# RGMII_SDIO_I2S.net
KiCad netlist of a schematic drawn in Altium Designer
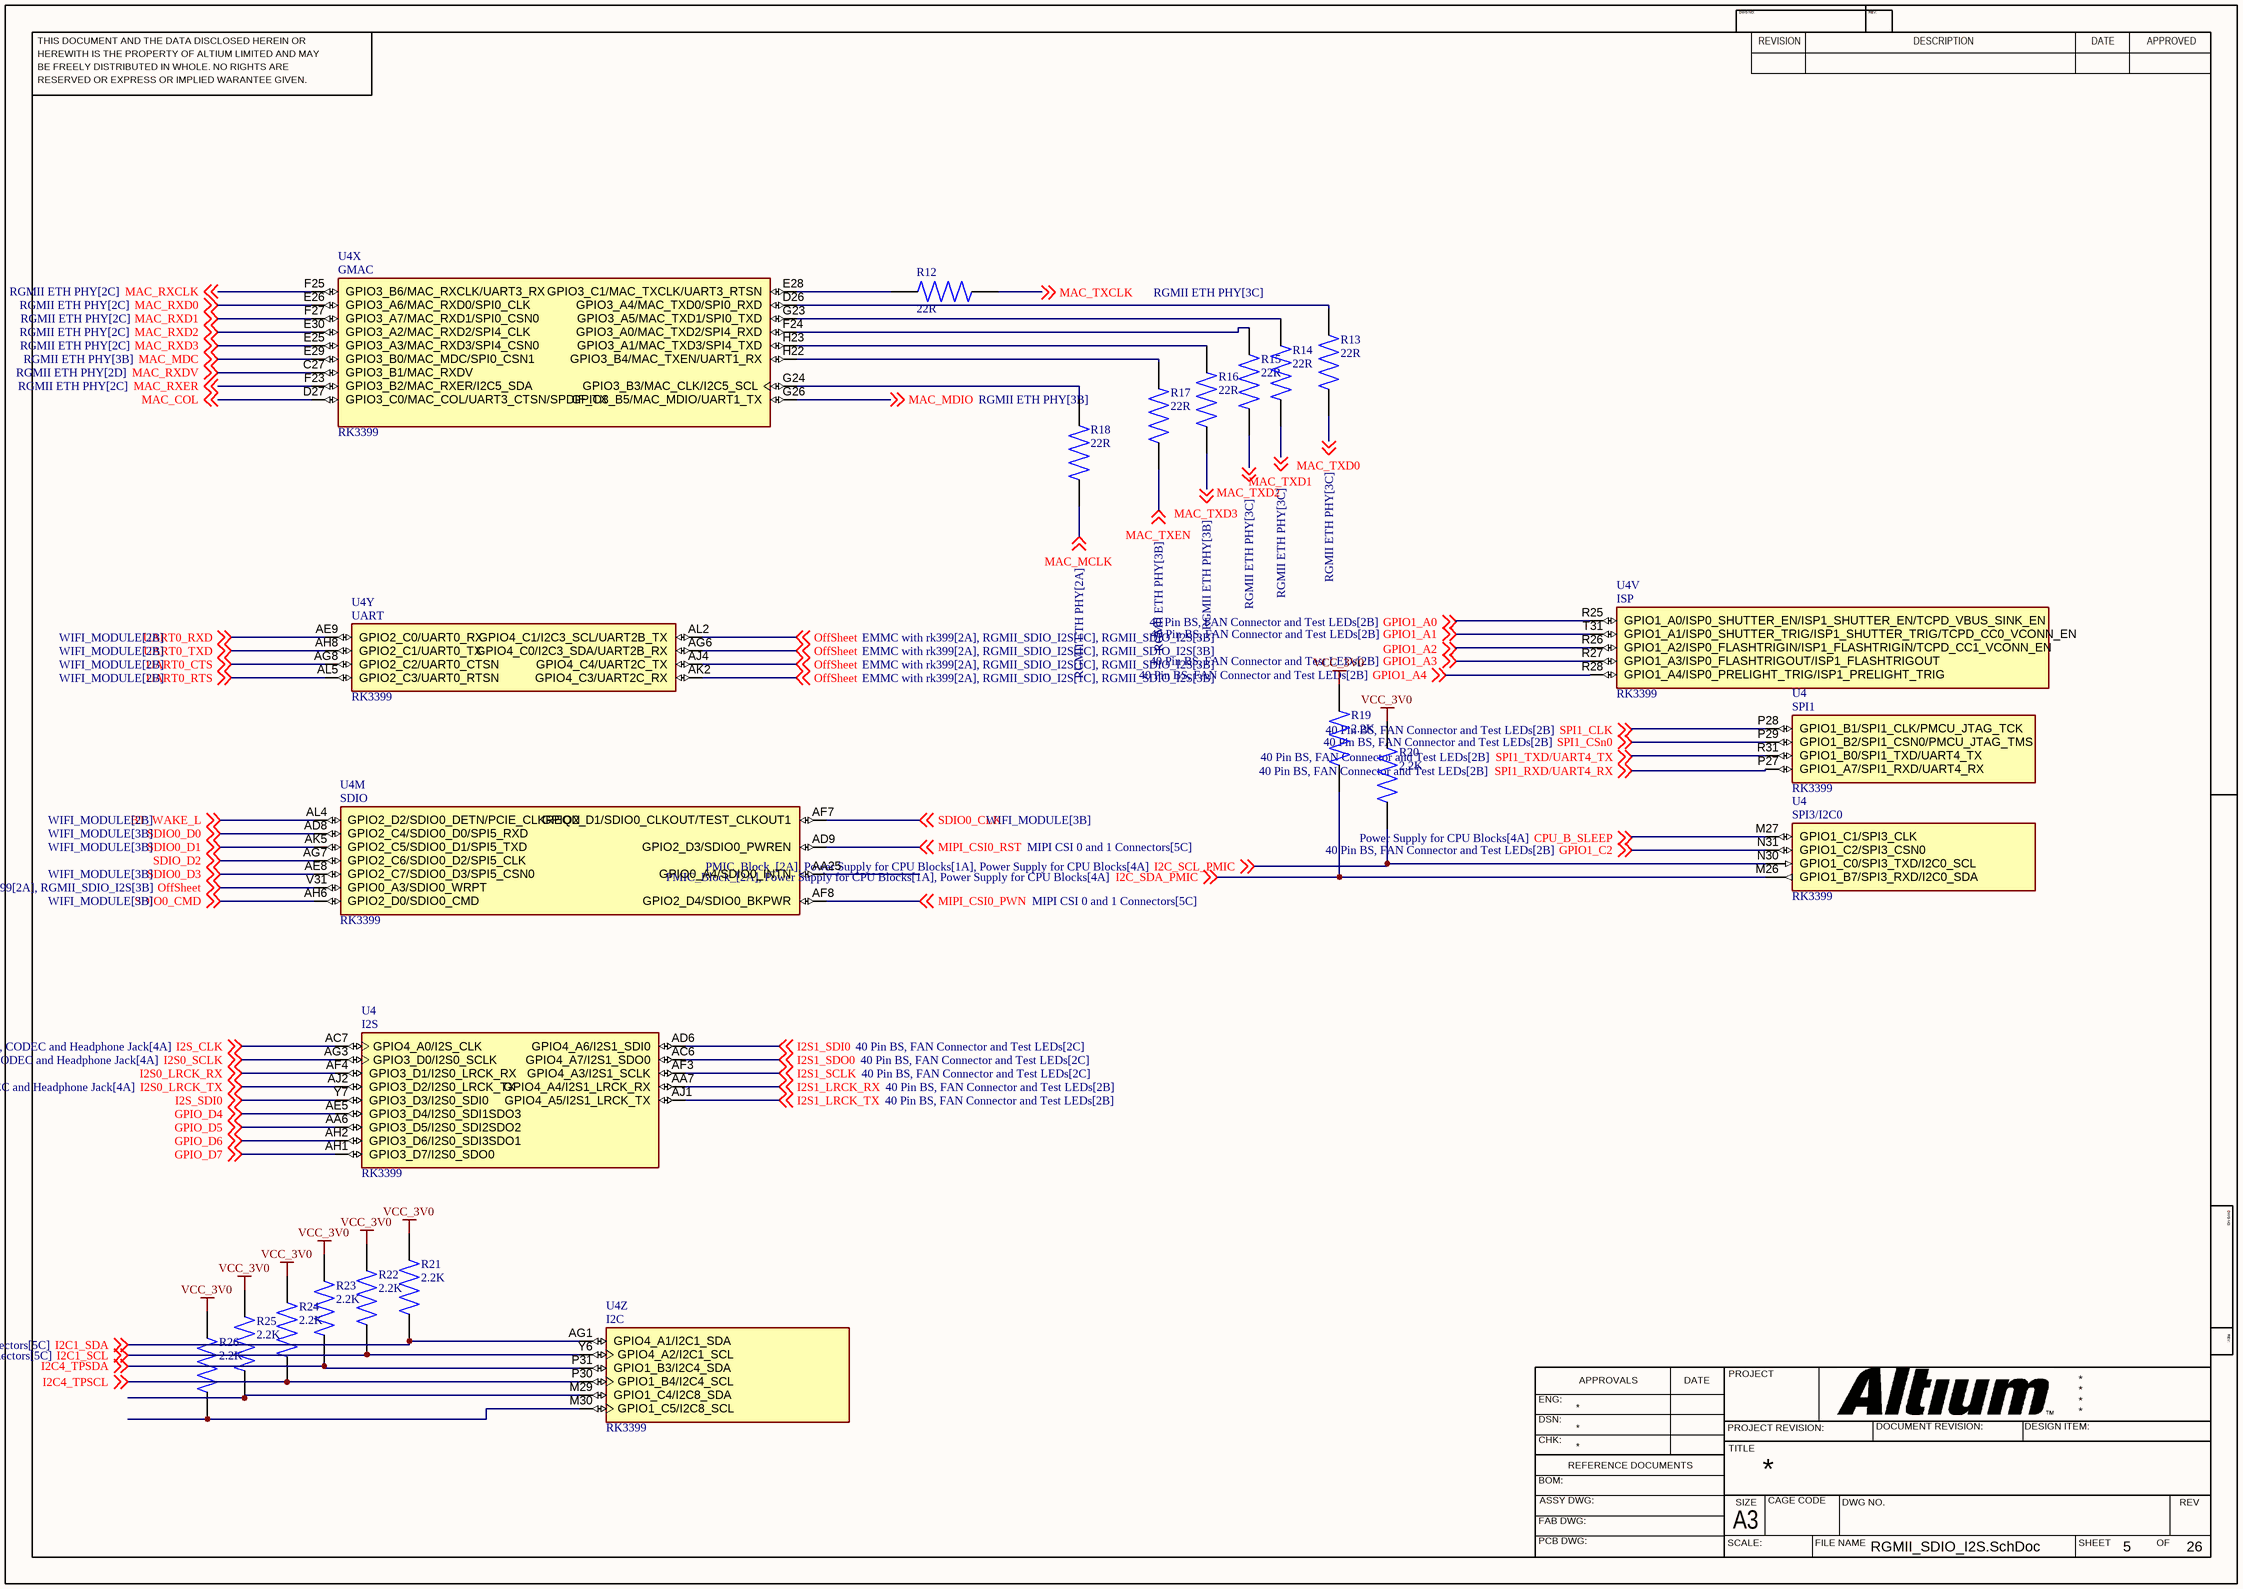
[diagram p0: RGMII_SDIO_I2S.SchDoc]

(export (version "E")
  (design (tool "Eeschema 10.0.6"))
  (components
    (comp (ref "R12")
      (value "22R")
      (footprint "RES_ERA6AHD330V")
      (fields (field (name "MP") "ERA6AHD330V"))
      (libsource (lib "ERA6AHD330V") (part "ERA6AHD330V"))
    )
    (comp (ref "R13")
      (value "22R")
      (footprint "RES_ERA6AHD330V")
      (fields (field (name "MP") "ERA6AHD330V"))
      (libsource (lib "ERA6AHD330V") (part "ERA6AHD330V"))
    )
    (comp (ref "R14")
      (value "22R")
      (footprint "RES_ERA6AHD330V")
      (fields (field (name "MP") "ERA6AHD330V"))
      (libsource (lib "ERA6AHD330V") (part "ERA6AHD330V"))
    )
    (comp (ref "R15")
      (value "22R")
      (footprint "RES_ERA6AHD330V")
      (fields (field (name "MP") "ERA6AHD330V"))
      (libsource (lib "ERA6AHD330V") (part "ERA6AHD330V"))
    )
    (comp (ref "R16")
      (value "22R")
      (footprint "RES_ERA6AHD330V")
      (fields (field (name "MP") "ERA6AHD330V"))
      (libsource (lib "ERA6AHD330V") (part "ERA6AHD330V"))
    )
    (comp (ref "R17")
      (value "22R")
      (footprint "RES_ERA6AHD330V")
      (fields (field (name "MP") "ERA6AHD330V"))
      (libsource (lib "ERA6AHD330V") (part "ERA6AHD330V"))
    )
    (comp (ref "R18")
      (value "22R")
      (footprint "RES_ERA6AHD330V")
      (fields (field (name "MP") "ERA6AHD330V"))
      (libsource (lib "ERA6AHD330V") (part "ERA6AHD330V"))
    )
    (comp (ref "R19")
      (value "2.2K")
      (footprint "RES_ERA8APB222V")
      (fields (field (name "MP") "ERA8APB222V"))
      (libsource (lib "ERA8APB222V") (part "ERA8APB222V"))
    )
    (comp (ref "R20")
      (value "2.2K")
      (footprint "RES_ERA8APB222V")
      (fields (field (name "MP") "ERA8APB222V"))
      (libsource (lib "ERA8APB222V") (part "ERA8APB222V"))
    )
    (comp (ref "R21")
      (value "2.2K")
      (footprint "RES_ERA8APB222V")
      (fields (field (name "MP") "ERA8APB222V"))
      (libsource (lib "ERA8APB222V") (part "ERA8APB222V"))
    )
    (comp (ref "R22")
      (value "2.2K")
      (footprint "RES_ERA8APB222V")
      (fields (field (name "MP") "ERA8APB222V"))
      (libsource (lib "ERA8APB222V") (part "ERA8APB222V"))
    )
    (comp (ref "R23")
      (value "2.2K")
      (footprint "RES_ERA8APB222V")
      (fields (field (name "MP") "ERA8APB222V"))
      (libsource (lib "ERA8APB222V") (part "ERA8APB222V"))
    )
    (comp (ref "R24")
      (value "2.2K")
      (footprint "RES_ERA8APB222V")
      (fields (field (name "MP") "ERA8APB222V"))
      (libsource (lib "ERA8APB222V") (part "ERA8APB222V"))
    )
    (comp (ref "R25")
      (value "2.2K")
      (footprint "RES_ERA8APB222V")
      (fields (field (name "MP") "ERA8APB222V"))
      (libsource (lib "ERA8APB222V") (part "ERA8APB222V"))
    )
    (comp (ref "R26")
      (value "2.2K")
      (footprint "RES_ERA8APB222V")
      (fields (field (name "MP") "ERA8APB222V"))
      (libsource (lib "ERA8APB222V") (part "ERA8APB222V"))
    )
    (comp (ref "U4")
      (value "RK3399")
      (footprint "BGA828C65P31X31_2100X2100X161N")
      (description "RK3399 ROCK Pi 4 Model A 2GB - ARMÂ® CortexÂ®-A53, CortexÂ®-A72 MPU Embedded Evaluation Board")
      (fields (field (name "MF") "Rockchip"))
      (libsource (lib "RK3399") (part "RK3399"))
    )
  )
  (nets
    (net (code "1") (name "BT_WAKE_L") (class "Default")
      (node (ref "U4") (pin "AL4") (pinfunction "GPIO2_D2/SDIO0_DETN/PCIE_CLKREQN_AL4") (pintype "bidirectional"))
    )
    (net (code "2") (name "CPU_B_SLEEP") (class "Default")
      (node (ref "U4") (pin "M27") (pinfunction "GPIO1_C1/SPI3_CLK_M27") (pintype "bidirectional"))
    )
    (net (code "3") (name "GPIO1_A0") (class "Default")
      (node (ref "U4") (pin "R25") (pinfunction "GPIO1_A0/ISP0_SHUTTER_EN/ISP1_SHUTTER_EN/TCPD_VBUS_SINK_EN_R25") (pintype "bidirectional"))
    )
    (net (code "4") (name "GPIO1_A1") (class "Default")
      (node (ref "U4") (pin "T31") (pinfunction "GPIO1_A1/ISP0_SHUTTER_TRIG/ISP1_SHUTTER_TRIG/TCPD_CC0_VCONN_EN_T31") (pintype "bidirectional"))
    )
    (net (code "5") (name "GPIO1_A2") (class "Default")
      (node (ref "U4") (pin "R26") (pinfunction "GPIO1_A2/ISP0_FLASHTRIGIN/ISP1_FLASHTRIGIN/TCPD_CC1_VCONN_EN_R26") (pintype "bidirectional"))
    )
    (net (code "6") (name "GPIO1_A3") (class "Default")
      (node (ref "U4") (pin "R27") (pinfunction "GPIO1_A3/ISP0_FLASHTRIGOUT/ISP1_FLASHTRIGOUT_R27") (pintype "bidirectional"))
    )
    (net (code "7") (name "GPIO1_A4") (class "Default")
      (node (ref "U4") (pin "R28") (pinfunction "GPIO1_A4/ISP0_PRELIGHT_TRIG/ISP1_PRELIGHT_TRIG_R28") (pintype "bidirectional"))
    )
    (net (code "8") (name "GPIO1_C2") (class "Default")
      (node (ref "U4") (pin "N31") (pinfunction "GPIO1_C2/SPI3_CSN0_N31") (pintype "bidirectional"))
    )
    (net (code "9") (name "GPIO_D4") (class "Default")
      (node (ref "U4") (pin "AE5") (pinfunction "GPIO3_D4/I2S0_SDI1SDO3_AE5") (pintype "bidirectional"))
    )
    (net (code "10") (name "GPIO_D5") (class "Default")
      (node (ref "U4") (pin "AA6") (pinfunction "GPIO3_D5/I2S0_SDI2SDO2_AA6") (pintype "bidirectional"))
    )
    (net (code "11") (name "GPIO_D6") (class "Default")
      (node (ref "U4") (pin "AH2") (pinfunction "GPIO3_D6/I2S0_SDI3SDO1_AH2") (pintype "bidirectional"))
    )
    (net (code "12") (name "GPIO_D7") (class "Default")
      (node (ref "U4") (pin "AH1") (pinfunction "GPIO3_D7/I2S0_SDO0_AH1") (pintype "bidirectional"))
    )
    (net (code "13") (name "I2C1_SCL") (class "Default")
      (node (ref "R22") (pin "1") (pinfunction "1_1") (pintype "passive"))
      (node (ref "U4") (pin "Y6") (pinfunction "GPIO4_A2/I2C1_SCL_Y6") (pintype "bidirectional"))
    )
    (net (code "14") (name "I2C1_SDA") (class "Default")
      (node (ref "R21") (pin "1") (pinfunction "1_1") (pintype "passive"))
      (node (ref "U4") (pin "AG1") (pinfunction "GPIO4_A1/I2C1_SDA_AG1") (pintype "bidirectional"))
    )
    (net (code "15") (name "I2C4_TPSCL") (class "Default")
      (node (ref "R24") (pin "1") (pinfunction "1_1") (pintype "passive"))
      (node (ref "U4") (pin "P30") (pinfunction "GPIO1_B4/I2C4_SCL_P30") (pintype "bidirectional"))
    )
    (net (code "16") (name "I2C4_TPSDA") (class "Default")
      (node (ref "R23") (pin "1") (pinfunction "1_1") (pintype "passive"))
      (node (ref "U4") (pin "P31") (pinfunction "GPIO1_B3/I2C4_SDA_P31") (pintype "bidirectional"))
    )
    (net (code "17") (name "I2C_SCL_PMIC") (class "Default")
      (node (ref "R20") (pin "1") (pinfunction "1_1") (pintype "passive"))
      (node (ref "U4") (pin "N30") (pinfunction "GPIO1_C0/SPI3_TXD/I2C0_SCL_N30") (pintype "input"))
    )
    (net (code "18") (name "I2C_SDA_PMIC") (class "Default")
      (node (ref "R19") (pin "1") (pinfunction "1_1") (pintype "passive"))
      (node (ref "U4") (pin "M26") (pinfunction "GPIO1_B7/SPI3_RXD/I2C0_SDA_M26") (pintype "output"))
    )
    (net (code "19") (name "I2S0_LRCK_RX") (class "Default")
      (node (ref "U4") (pin "AF4") (pinfunction "GPIO3_D1/I2S0_LRCK_RX_AF4") (pintype "bidirectional"))
    )
    (net (code "20") (name "I2S0_LRCK_TX") (class "Default")
      (node (ref "U4") (pin "AJ2") (pinfunction "GPIO3_D2/I2S0_LRCK_TX_AJ2") (pintype "bidirectional"))
    )
    (net (code "21") (name "I2S0_SCLK") (class "Default")
      (node (ref "U4") (pin "AG3") (pinfunction "GPIO3_D0/I2S0_SCLK_AG3") (pintype "bidirectional"))
    )
    (net (code "22") (name "I2S1_LRCK_RX") (class "Default")
      (node (ref "U4") (pin "AA7") (pinfunction "GPIO4_A4/I2S1_LRCK_RX_AA7") (pintype "bidirectional"))
    )
    (net (code "23") (name "I2S1_LRCK_TX") (class "Default")
      (node (ref "U4") (pin "AJ1") (pinfunction "GPIO4_A5/I2S1_LRCK_TX_AJ1") (pintype "bidirectional"))
    )
    (net (code "24") (name "I2S1_SCLK") (class "Default")
      (node (ref "U4") (pin "AF3") (pinfunction "GPIO4_A3/I2S1_SCLK_AF3") (pintype "bidirectional"))
    )
    (net (code "25") (name "I2S1_SDI0") (class "Default")
      (node (ref "U4") (pin "AD6") (pinfunction "GPIO4_A6/I2S1_SDI0_AD6") (pintype "bidirectional"))
    )
    (net (code "26") (name "I2S1_SDO0") (class "Default")
      (node (ref "U4") (pin "AC6") (pinfunction "GPIO4_A7/I2S1_SDO0_AC6") (pintype "bidirectional"))
    )
    (net (code "27") (name "I2S_CLK") (class "Default")
      (node (ref "U4") (pin "AC7") (pinfunction "GPIO4_A0/I2S_CLK_AC7") (pintype "bidirectional"))
    )
    (net (code "28") (name "I2S_SDI0") (class "Default")
      (node (ref "U4") (pin "Y7") (pinfunction "GPIO3_D3/I2S0_SDI0_Y7") (pintype "bidirectional"))
    )
    (net (code "29") (name "MAC_COL") (class "Default")
      (node (ref "U4") (pin "D27") (pinfunction "GPIO3_C0/MAC_COL/UART3_CTSN/SPDIF_TX_D27") (pintype "bidirectional"))
    )
    (net (code "30") (name "MAC_MCLK") (class "Default")
      (node (ref "R18") (pin "1") (pinfunction "1_1") (pintype "passive"))
    )
    (net (code "31") (name "MAC_MDC") (class "Default")
      (node (ref "U4") (pin "E29") (pinfunction "GPIO3_B0/MAC_MDC/SPI0_CSN1_E29") (pintype "bidirectional"))
    )
    (net (code "32") (name "MAC_MDIO") (class "Default")
      (node (ref "U4") (pin "G26") (pinfunction "GPIO3_B5/MAC_MDIO/UART1_TX_G26") (pintype "bidirectional"))
    )
    (net (code "33") (name "MAC_RXCLK") (class "Default")
      (node (ref "U4") (pin "F25") (pinfunction "GPIO3_B6/MAC_RXCLK/UART3_RX_F25") (pintype "bidirectional"))
    )
    (net (code "34") (name "MAC_RXD0") (class "Default")
      (node (ref "U4") (pin "E26") (pinfunction "GPIO3_A6/MAC_RXD0/SPI0_CLK_E26") (pintype "bidirectional"))
    )
    (net (code "35") (name "MAC_RXD1") (class "Default")
      (node (ref "U4") (pin "F27") (pinfunction "GPIO3_A7/MAC_RXD1/SPI0_CSN0_F27") (pintype "bidirectional"))
    )
    (net (code "36") (name "MAC_RXD2") (class "Default")
      (node (ref "U4") (pin "E30") (pinfunction "GPIO3_A2/MAC_RXD2/SPI4_CLK_E30") (pintype "bidirectional"))
    )
    (net (code "37") (name "MAC_RXD3") (class "Default")
      (node (ref "U4") (pin "E25") (pinfunction "GPIO3_A3/MAC_RXD3/SPI4_CSN0_E25") (pintype "bidirectional"))
    )
    (net (code "38") (name "MAC_RXDV") (class "Default")
      (node (ref "U4") (pin "C27") (pinfunction "GPIO3_B1/MAC_RXDV_C27") (pintype "bidirectional"))
    )
    (net (code "39") (name "MAC_RXER") (class "Default")
      (node (ref "U4") (pin "F23") (pinfunction "GPIO3_B2/MAC_RXER/I2C5_SDA_F23") (pintype "bidirectional"))
    )
    (net (code "40") (name "MAC_TXCLK") (class "Default")
      (node (ref "R12") (pin "1") (pinfunction "1_1") (pintype "passive"))
    )
    (net (code "41") (name "MAC_TXD0") (class "Default")
      (node (ref "R13") (pin "1") (pinfunction "1_1") (pintype "passive"))
    )
    (net (code "42") (name "MAC_TXD1") (class "Default")
      (node (ref "R14") (pin "1") (pinfunction "1_1") (pintype "passive"))
    )
    (net (code "43") (name "MAC_TXD2") (class "Default")
      (node (ref "R15") (pin "1") (pinfunction "1_1") (pintype "passive"))
    )
    (net (code "44") (name "MAC_TXD3") (class "Default")
      (node (ref "R16") (pin "1") (pinfunction "1_1") (pintype "passive"))
    )
    (net (code "45") (name "MAC_TXEN") (class "Default")
      (node (ref "R17") (pin "1") (pinfunction "1_1") (pintype "passive"))
    )
    (net (code "46") (name "MIPI_CSI0_PWN") (class "Default")
      (node (ref "U4") (pin "AF8") (pinfunction "GPIO2_D4/SDIO0_BKPWR_AF8") (pintype "bidirectional"))
    )
    (net (code "47") (name "MIPI_CSI0_RST") (class "Default")
      (node (ref "U4") (pin "AD9") (pinfunction "GPIO2_D3/SDIO0_PWREN_AD9") (pintype "bidirectional"))
    )
    (net (code "48") (name "Net-(U4X-GPIO3_A0{slash}MAC_TXD2{slash}SPI4_RXD)") (class "Default")
      (node (ref "R15") (pin "2") (pinfunction "2_2") (pintype "passive"))
      (node (ref "U4") (pin "F24") (pinfunction "GPIO3_A0/MAC_TXD2/SPI4_RXD_F24") (pintype "bidirectional"))
    )
    (net (code "49") (name "Net-(U4X-GPIO3_A1{slash}MAC_TXD3{slash}SPI4_TXD)") (class "Default")
      (node (ref "R16") (pin "2") (pinfunction "2_2") (pintype "passive"))
      (node (ref "U4") (pin "H23") (pinfunction "GPIO3_A1/MAC_TXD3/SPI4_TXD_H23") (pintype "bidirectional"))
    )
    (net (code "50") (name "Net-(U4X-GPIO3_A4{slash}MAC_TXD0{slash}SPI0_RXD)") (class "Default")
      (node (ref "R13") (pin "2") (pinfunction "2_2") (pintype "passive"))
      (node (ref "U4") (pin "D26") (pinfunction "GPIO3_A4/MAC_TXD0/SPI0_RXD_D26") (pintype "bidirectional"))
    )
    (net (code "51") (name "Net-(U4X-GPIO3_A5{slash}MAC_TXD1{slash}SPI0_TXD)") (class "Default")
      (node (ref "R14") (pin "2") (pinfunction "2_2") (pintype "passive"))
      (node (ref "U4") (pin "G23") (pinfunction "GPIO3_A5/MAC_TXD1/SPI0_TXD_G23") (pintype "bidirectional"))
    )
    (net (code "52") (name "Net-(U4X-GPIO3_B3{slash}MAC_CLK{slash}I2C5_SCL)") (class "Default")
      (node (ref "R18") (pin "2") (pinfunction "2_2") (pintype "passive"))
      (node (ref "U4") (pin "G24") (pinfunction "GPIO3_B3/MAC_CLK/I2C5_SCL_G24") (pintype "bidirectional"))
    )
    (net (code "53") (name "Net-(U4X-GPIO3_B4{slash}MAC_TXEN{slash}UART1_RX)") (class "Default")
      (node (ref "R17") (pin "2") (pinfunction "2_2") (pintype "passive"))
      (node (ref "U4") (pin "H22") (pinfunction "GPIO3_B4/MAC_TXEN/UART1_RX_H22") (pintype "bidirectional"))
    )
    (net (code "54") (name "Net-(U4X-GPIO3_C1{slash}MAC_TXCLK{slash}UART3_RTSN)") (class "Default")
      (node (ref "R12") (pin "2") (pinfunction "2_2") (pintype "passive"))
      (node (ref "U4") (pin "E28") (pinfunction "GPIO3_C1/MAC_TXCLK/UART3_RTSN_E28") (pintype "bidirectional"))
    )
    (net (code "55") (name "Net-(U4Z-GPIO1_C4{slash}I2C8_SDA)") (class "Default")
      (node (ref "R25") (pin "1") (pinfunction "1_1") (pintype "passive"))
      (node (ref "U4") (pin "M29") (pinfunction "GPIO1_C4/I2C8_SDA_M29") (pintype "bidirectional"))
    )
    (net (code "56") (name "Net-(U4Z-GPIO1_C5{slash}I2C8_SCL)") (class "Default")
      (node (ref "R26") (pin "1") (pinfunction "1_1") (pintype "passive"))
      (node (ref "U4") (pin "M30") (pinfunction "GPIO1_C5/I2C8_SCL_M30") (pintype "bidirectional"))
    )
    (net (code "57") (name "OffSheet") (class "Default")
      (node (ref "U4") (pin "AG6") (pinfunction "GPIO4_C0/I2C3_SDA/UART2B_RX_AG6") (pintype "bidirectional"))
      (node (ref "U4") (pin "AJ4") (pinfunction "GPIO4_C4/UART2C_TX_AJ4") (pintype "bidirectional"))
      (node (ref "U4") (pin "AK2") (pinfunction "GPIO4_C3/UART2C_RX_AK2") (pintype "bidirectional"))
      (node (ref "U4") (pin "AL2") (pinfunction "GPIO4_C1/I2C3_SCL/UART2B_TX_AL2") (pintype "bidirectional"))
      (node (ref "U4") (pin "V31") (pinfunction "GPIO0_A3/SDIO0_WRPT_V31") (pintype "bidirectional"))
    )
    (net (code "58") (name "SDIO0_CLK") (class "Default")
      (node (ref "U4") (pin "AF7") (pinfunction "GPIO2_D1/SDIO0_CLKOUT/TEST_CLKOUT1_AF7") (pintype "bidirectional"))
    )
    (net (code "59") (name "SDIO0_CMD") (class "Default")
      (node (ref "U4") (pin "AH6") (pinfunction "GPIO2_D0/SDIO0_CMD_AH6") (pintype "bidirectional"))
    )
    (net (code "60") (name "SDIO0_D0") (class "Default")
      (node (ref "U4") (pin "AD8") (pinfunction "GPIO2_C4/SDIO0_D0/SPI5_RXD_AD8") (pintype "bidirectional"))
    )
    (net (code "61") (name "SDIO0_D1") (class "Default")
      (node (ref "U4") (pin "AK5") (pinfunction "GPIO2_C5/SDIO0_D1/SPI5_TXD_AK5") (pintype "bidirectional"))
    )
    (net (code "62") (name "SDIO0_D3") (class "Default")
      (node (ref "U4") (pin "AE8") (pinfunction "GPIO2_C7/SDIO0_D3/SPI5_CSN0_AE8") (pintype "bidirectional"))
    )
    (net (code "63") (name "SDIO_D2") (class "Default")
      (node (ref "U4") (pin "AG7") (pinfunction "GPIO2_C6/SDIO0_D2/SPI5_CLK_AG7") (pintype "bidirectional"))
    )
    (net (code "64") (name "SPI1_CLK") (class "Default")
      (node (ref "U4") (pin "P28") (pinfunction "GPIO1_B1/SPI1_CLK/PMCU_JTAG_TCK_P28") (pintype "bidirectional"))
    )
    (net (code "65") (name "SPI1_CSn0") (class "Default")
      (node (ref "U4") (pin "P29") (pinfunction "GPIO1_B2/SPI1_CSN0/PMCU_JTAG_TMS_P29") (pintype "bidirectional"))
    )
    (net (code "66") (name "SPI1_RXD{slash}UART4_RX") (class "Default")
      (node (ref "U4") (pin "P27") (pinfunction "GPIO1_A7/SPI1_RXD/UART4_RX_P27") (pintype "bidirectional"))
    )
    (net (code "67") (name "SPI1_TXD{slash}UART4_TX") (class "Default")
      (node (ref "U4") (pin "R31") (pinfunction "GPIO1_B0/SPI1_TXD/UART4_TX_R31") (pintype "bidirectional"))
    )
    (net (code "68") (name "UART0_CTS") (class "Default")
      (node (ref "U4") (pin "AG8") (pinfunction "GPIO2_C2/UART0_CTSN_AG8") (pintype "bidirectional"))
    )
    (net (code "69") (name "UART0_RTS") (class "Default")
      (node (ref "U4") (pin "AL5") (pinfunction "GPIO2_C3/UART0_RTSN_AL5") (pintype "bidirectional"))
    )
    (net (code "70") (name "UART0_RXD") (class "Default")
      (node (ref "U4") (pin "AE9") (pinfunction "GPIO2_C0/UART0_RX_AE9") (pintype "bidirectional"))
    )
    (net (code "71") (name "UART0_TXD") (class "Default")
      (node (ref "U4") (pin "AH8") (pinfunction "GPIO2_C1/UART0_TX_AH8") (pintype "bidirectional"))
    )
    (net (code "72") (name "VCC_3V0") (class "Default")
      (node (ref "R19") (pin "2") (pinfunction "2_2") (pintype "passive"))
      (node (ref "R20") (pin "2") (pinfunction "2_2") (pintype "passive"))
      (node (ref "R21") (pin "2") (pinfunction "2_2") (pintype "passive"))
      (node (ref "R22") (pin "2") (pinfunction "2_2") (pintype "passive"))
      (node (ref "R23") (pin "2") (pinfunction "2_2") (pintype "passive"))
      (node (ref "R24") (pin "2") (pinfunction "2_2") (pintype "passive"))
      (node (ref "R25") (pin "2") (pinfunction "2_2") (pintype "passive"))
      (node (ref "R26") (pin "2") (pinfunction "2_2") (pintype "passive"))
    )
    (net (code "73") (name "unconnected-(U4M-GPIO0_A4{slash}SDIO0_INTN-PadAA25)") (class "Default")
      (node (ref "U4") (pin "AA25") (pinfunction "GPIO0_A4/SDIO0_INTN_AA25") (pintype "bidirectional"))
    )
  )
)
